# cpx-synth1-jacksA.net
KiCad netlist of a schematic drawn in EAGLE
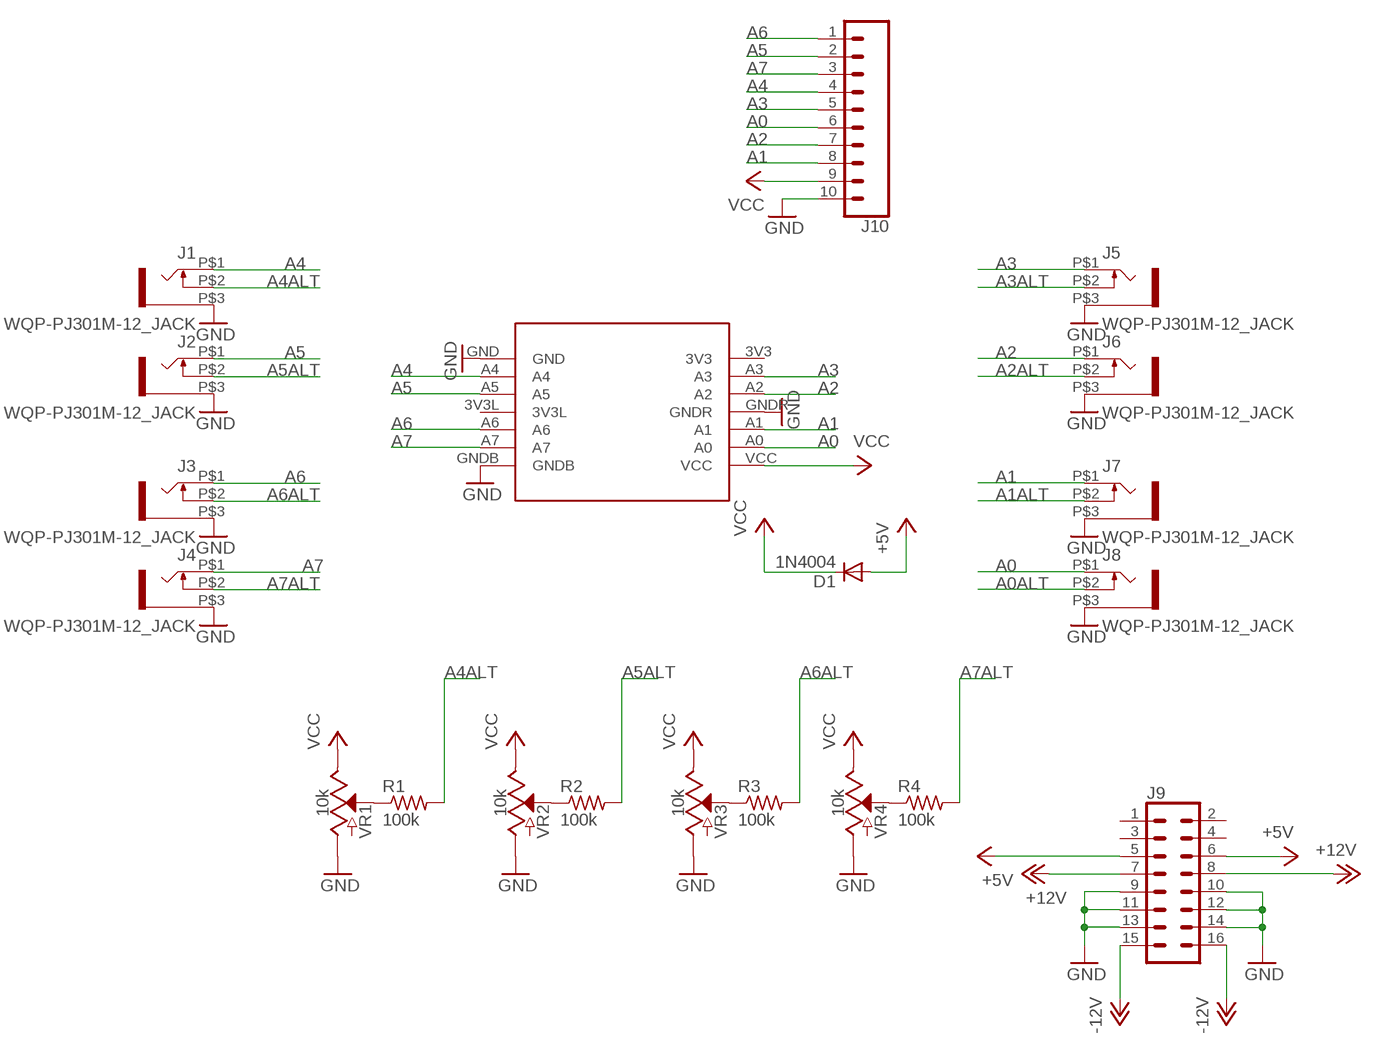
[diagram p0: schematic, sheet 1]

(export (version "E")
  (design (tool "Eeschema 10.0.6"))
  (components
    (comp (ref "D1")
      (value "1N4004")
      (footprint "eagle-import:DO41-10")
      (libsource (lib "eagle-import") (part "1N4004"))
    )
    (comp (ref "J1")
      (value "WQP-PJ301M-12_JACK")
      (footprint "eagle-import:WQP-PJ301M-12_JACK")
      (libsource (lib "eagle-import") (part "WQP-PJ301M-12_JACK"))
    )
    (comp (ref "J2")
      (value "WQP-PJ301M-12_JACK")
      (footprint "eagle-import:WQP-PJ301M-12_JACK")
      (libsource (lib "eagle-import") (part "WQP-PJ301M-12_JACK"))
    )
    (comp (ref "J3")
      (value "WQP-PJ301M-12_JACK")
      (footprint "eagle-import:WQP-PJ301M-12_JACK")
      (libsource (lib "eagle-import") (part "WQP-PJ301M-12_JACK"))
    )
    (comp (ref "J4")
      (value "WQP-PJ301M-12_JACK")
      (footprint "eagle-import:WQP-PJ301M-12_JACK")
      (libsource (lib "eagle-import") (part "WQP-PJ301M-12_JACK"))
    )
    (comp (ref "J5")
      (value "WQP-PJ301M-12_JACK")
      (footprint "eagle-import:WQP-PJ301M-12_JACK")
      (libsource (lib "eagle-import") (part "WQP-PJ301M-12_JACK"))
    )
    (comp (ref "J6")
      (value "WQP-PJ301M-12_JACK")
      (footprint "eagle-import:WQP-PJ301M-12_JACK")
      (libsource (lib "eagle-import") (part "WQP-PJ301M-12_JACK"))
    )
    (comp (ref "J7")
      (value "WQP-PJ301M-12_JACK")
      (footprint "eagle-import:WQP-PJ301M-12_JACK")
      (libsource (lib "eagle-import") (part "WQP-PJ301M-12_JACK"))
    )
    (comp (ref "J8")
      (value "WQP-PJ301M-12_JACK")
      (footprint "eagle-import:WQP-PJ301M-12_JACK")
      (libsource (lib "eagle-import") (part "WQP-PJ301M-12_JACK"))
    )
    (comp (ref "J9")
      (value "CONN_08X2")
      (footprint "eagle-import:2X8")
      (libsource (lib "eagle-import") (part "CONN_08X2"))
    )
    (comp (ref "J10")
      (value "CONN_10\"")
      (footprint "eagle-import:1X10")
      (libsource (lib "eagle-import") (part "CONN_10{dblquote}"))
    )
    (comp (ref "R1")
      (value "100k")
      (footprint "eagle-import:R0603")
      (libsource (lib "eagle-import") (part "R-US_R0603"))
    )
    (comp (ref "R2")
      (value "100k")
      (footprint "eagle-import:R0603")
      (libsource (lib "eagle-import") (part "R-US_R0603"))
    )
    (comp (ref "R3")
      (value "100k")
      (footprint "eagle-import:R0603")
      (libsource (lib "eagle-import") (part "R-US_R0603"))
    )
    (comp (ref "R4")
      (value "100k")
      (footprint "eagle-import:R0603")
      (libsource (lib "eagle-import") (part "R-US_R0603"))
    )
    (comp (ref "U1")
      (value "CIRCUITPLAYGROUNDEXPRESS")
      (footprint "eagle-import:CIRCUITPLAYGROUNDEXPRESS")
      (libsource (lib "eagle-import") (part "CIRCUITPLAYGROUNDEXPRESS"))
    )
    (comp (ref "VR1")
      (value "10k")
      (footprint "eagle-import:POT-PTH-ALPS-KIT")
      (libsource (lib "eagle-import") (part "POTENTIOMETER-PTH-9MM-1/20W-20%-KIT"))
    )
    (comp (ref "VR2")
      (value "10k")
      (footprint "eagle-import:POT-PTH-ALPS-KIT")
      (libsource (lib "eagle-import") (part "POTENTIOMETER-PTH-9MM-1/20W-20%-KIT"))
    )
    (comp (ref "VR3")
      (value "10k")
      (footprint "eagle-import:POT-PTH-ALPS-KIT")
      (libsource (lib "eagle-import") (part "POTENTIOMETER-PTH-9MM-1/20W-20%-KIT"))
    )
    (comp (ref "VR4")
      (value "10k")
      (footprint "eagle-import:POT-PTH-ALPS-KIT")
      (libsource (lib "eagle-import") (part "POTENTIOMETER-PTH-9MM-1/20W-20%-KIT"))
    )
  )
  (nets
    (net (code "1") (name "+5V") (class "Default")
      (node (ref "D1") (pin "A") (pinfunction "A_A") (pintype "passive"))
      (node (ref "J9") (pin "5") (pinfunction "5_5") (pintype "passive"))
      (node (ref "J9") (pin "6") (pinfunction "6_6") (pintype "passive"))
    )
    (net (code "2") (name "+12V") (class "Default")
      (node (ref "J9") (pin "7") (pinfunction "7_7") (pintype "passive"))
      (node (ref "J9") (pin "8") (pinfunction "8_8") (pintype "passive"))
    )
    (net (code "3") (name "-12V") (class "Default")
      (node (ref "J9") (pin "15") (pinfunction "15_15") (pintype "passive"))
      (node (ref "J9") (pin "16") (pinfunction "16_16") (pintype "passive"))
    )
    (net (code "4") (name "/A0") (class "Default")
      (node (ref "J10") (pin "6") (pinfunction "6_6") (pintype "passive"))
      (node (ref "J8") (pin "P$1") (pinfunction "2_P$1") (pintype "passive"))
      (node (ref "U1") (pin "A0") (pinfunction "A0_A0") (pintype "bidirectional"))
    )
    (net (code "5") (name "/A0ALT") (class "Default")
      (node (ref "J8") (pin "P$2") (pinfunction "3_P$2") (pintype "passive"))
    )
    (net (code "6") (name "/A1") (class "Default")
      (node (ref "J10") (pin "8") (pinfunction "8_8") (pintype "passive"))
      (node (ref "J7") (pin "P$1") (pinfunction "2_P$1") (pintype "passive"))
      (node (ref "U1") (pin "A1") (pinfunction "A1_A1") (pintype "bidirectional"))
    )
    (net (code "7") (name "/A1ALT") (class "Default")
      (node (ref "J7") (pin "P$2") (pinfunction "3_P$2") (pintype "passive"))
    )
    (net (code "8") (name "/A2") (class "Default")
      (node (ref "J10") (pin "7") (pinfunction "7_7") (pintype "passive"))
      (node (ref "J6") (pin "P$1") (pinfunction "2_P$1") (pintype "passive"))
      (node (ref "U1") (pin "A2") (pinfunction "A2_A2") (pintype "bidirectional"))
    )
    (net (code "9") (name "/A2ALT") (class "Default")
      (node (ref "J6") (pin "P$2") (pinfunction "3_P$2") (pintype "passive"))
    )
    (net (code "10") (name "/A3") (class "Default")
      (node (ref "J10") (pin "5") (pinfunction "5_5") (pintype "passive"))
      (node (ref "J5") (pin "P$1") (pinfunction "2_P$1") (pintype "passive"))
      (node (ref "U1") (pin "A3") (pinfunction "A3_A3") (pintype "bidirectional"))
    )
    (net (code "11") (name "/A3ALT") (class "Default")
      (node (ref "J5") (pin "P$2") (pinfunction "3_P$2") (pintype "passive"))
    )
    (net (code "12") (name "/A4") (class "Default")
      (node (ref "J1") (pin "P$1") (pinfunction "2_P$1") (pintype "passive"))
      (node (ref "J10") (pin "4") (pinfunction "4_4") (pintype "passive"))
      (node (ref "U1") (pin "A4") (pinfunction "A4_A4") (pintype "bidirectional"))
    )
    (net (code "13") (name "/A4ALT") (class "Default")
      (node (ref "J1") (pin "P$2") (pinfunction "3_P$2") (pintype "passive"))
      (node (ref "R1") (pin "2") (pinfunction "2_2") (pintype "passive"))
    )
    (net (code "14") (name "/A5") (class "Default")
      (node (ref "J10") (pin "2") (pinfunction "2_2") (pintype "passive"))
      (node (ref "J2") (pin "P$1") (pinfunction "2_P$1") (pintype "passive"))
      (node (ref "U1") (pin "A5") (pinfunction "A5_A5") (pintype "bidirectional"))
    )
    (net (code "15") (name "/A5ALT") (class "Default")
      (node (ref "J2") (pin "P$2") (pinfunction "3_P$2") (pintype "passive"))
      (node (ref "R2") (pin "2") (pinfunction "2_2") (pintype "passive"))
    )
    (net (code "16") (name "/A6") (class "Default")
      (node (ref "J10") (pin "1") (pinfunction "1_1") (pintype "passive"))
      (node (ref "J3") (pin "P$1") (pinfunction "2_P$1") (pintype "passive"))
      (node (ref "U1") (pin "A6") (pinfunction "A6_A6") (pintype "bidirectional"))
    )
    (net (code "17") (name "/A6ALT") (class "Default")
      (node (ref "J3") (pin "P$2") (pinfunction "3_P$2") (pintype "passive"))
      (node (ref "R3") (pin "2") (pinfunction "2_2") (pintype "passive"))
    )
    (net (code "18") (name "/A7") (class "Default")
      (node (ref "J10") (pin "3") (pinfunction "3_3") (pintype "passive"))
      (node (ref "J4") (pin "P$1") (pinfunction "2_P$1") (pintype "passive"))
      (node (ref "U1") (pin "A7") (pinfunction "A7_A7") (pintype "bidirectional"))
    )
    (net (code "19") (name "/A7ALT") (class "Default")
      (node (ref "J4") (pin "P$2") (pinfunction "3_P$2") (pintype "passive"))
      (node (ref "R4") (pin "2") (pinfunction "2_2") (pintype "passive"))
    )
    (net (code "20") (name "GND") (class "Default")
      (node (ref "J1") (pin "P$3") (pinfunction "1_P$3") (pintype "passive"))
      (node (ref "J10") (pin "10") (pinfunction "10_10") (pintype "passive"))
      (node (ref "J2") (pin "P$3") (pinfunction "1_P$3") (pintype "passive"))
      (node (ref "J3") (pin "P$3") (pinfunction "1_P$3") (pintype "passive"))
      (node (ref "J4") (pin "P$3") (pinfunction "1_P$3") (pintype "passive"))
      (node (ref "J5") (pin "P$3") (pinfunction "1_P$3") (pintype "passive"))
      (node (ref "J6") (pin "P$3") (pinfunction "1_P$3") (pintype "passive"))
      (node (ref "J7") (pin "P$3") (pinfunction "1_P$3") (pintype "passive"))
      (node (ref "J8") (pin "P$3") (pinfunction "1_P$3") (pintype "passive"))
      (node (ref "J9") (pin "10") (pinfunction "10_10") (pintype "passive"))
      (node (ref "J9") (pin "11") (pinfunction "11_11") (pintype "passive"))
      (node (ref "J9") (pin "12") (pinfunction "12_12") (pintype "passive"))
      (node (ref "J9") (pin "13") (pinfunction "13_13") (pintype "passive"))
      (node (ref "J9") (pin "14") (pinfunction "14_14") (pintype "passive"))
      (node (ref "J9") (pin "9") (pinfunction "9_9") (pintype "passive"))
      (node (ref "U1") (pin "GND") (pinfunction "GND_GND") (pintype "bidirectional"))
      (node (ref "U1") (pin "GNDB") (pinfunction "GNDB_GNDB") (pintype "bidirectional"))
      (node (ref "U1") (pin "GNDR") (pinfunction "GNDR_GNDR") (pintype "bidirectional"))
      (node (ref "VR1") (pin "P$3") (pinfunction "A_P$3") (pintype "passive"))
      (node (ref "VR2") (pin "P$3") (pinfunction "A_P$3") (pintype "passive"))
      (node (ref "VR3") (pin "P$3") (pinfunction "A_P$3") (pintype "passive"))
      (node (ref "VR4") (pin "P$3") (pinfunction "A_P$3") (pintype "passive"))
    )
    (net (code "21") (name "Net-(VR1-S)") (class "Default")
      (node (ref "R1") (pin "1") (pinfunction "1_1") (pintype "passive"))
      (node (ref "VR1") (pin "P$2") (pinfunction "S_P$2") (pintype "passive"))
    )
    (net (code "22") (name "Net-(VR2-S)") (class "Default")
      (node (ref "R2") (pin "1") (pinfunction "1_1") (pintype "passive"))
      (node (ref "VR2") (pin "P$2") (pinfunction "S_P$2") (pintype "passive"))
    )
    (net (code "23") (name "Net-(VR3-S)") (class "Default")
      (node (ref "R3") (pin "1") (pinfunction "1_1") (pintype "passive"))
      (node (ref "VR3") (pin "P$2") (pinfunction "S_P$2") (pintype "passive"))
    )
    (net (code "24") (name "Net-(VR4-S)") (class "Default")
      (node (ref "R4") (pin "1") (pinfunction "1_1") (pintype "passive"))
      (node (ref "VR4") (pin "P$2") (pinfunction "S_P$2") (pintype "passive"))
    )
    (net (code "25") (name "VCC") (class "Default")
      (node (ref "D1") (pin "C") (pinfunction "C_C") (pintype "passive"))
      (node (ref "J10") (pin "9") (pinfunction "9_9") (pintype "passive"))
      (node (ref "U1") (pin "VCC") (pinfunction "VCC_VCC") (pintype "bidirectional"))
      (node (ref "VR1") (pin "P$1") (pinfunction "E_P$1") (pintype "passive"))
      (node (ref "VR2") (pin "P$1") (pinfunction "E_P$1") (pintype "passive"))
      (node (ref "VR3") (pin "P$1") (pinfunction "E_P$1") (pintype "passive"))
      (node (ref "VR4") (pin "P$1") (pinfunction "E_P$1") (pintype "passive"))
    )
    (net (code "26") (name "unconnected-(J9-Pad1)") (class "Default")
      (node (ref "J9") (pin "1") (pinfunction "1_1") (pintype "passive"))
    )
    (net (code "27") (name "unconnected-(J9-Pad2)") (class "Default")
      (node (ref "J9") (pin "2") (pinfunction "2_2") (pintype "passive"))
    )
    (net (code "28") (name "unconnected-(J9-Pad3)") (class "Default")
      (node (ref "J9") (pin "3") (pinfunction "3_3") (pintype "passive"))
    )
    (net (code "29") (name "unconnected-(J9-Pad4)") (class "Default")
      (node (ref "J9") (pin "4") (pinfunction "4_4") (pintype "passive"))
    )
    (net (code "30") (name "unconnected-(U1-Pad3V3)") (class "Default")
      (node (ref "U1") (pin "3V3") (pinfunction "3V3_3V3") (pintype "bidirectional"))
    )
    (net (code "31") (name "unconnected-(U1-Pad3V3L)") (class "Default")
      (node (ref "U1") (pin "3V3L") (pinfunction "3V3L_3V3L") (pintype "bidirectional"))
    )
  )
)
